# LVGL_Free_RTOS.net
KiCad netlist of a schematic drawn in EasyEDA Pro
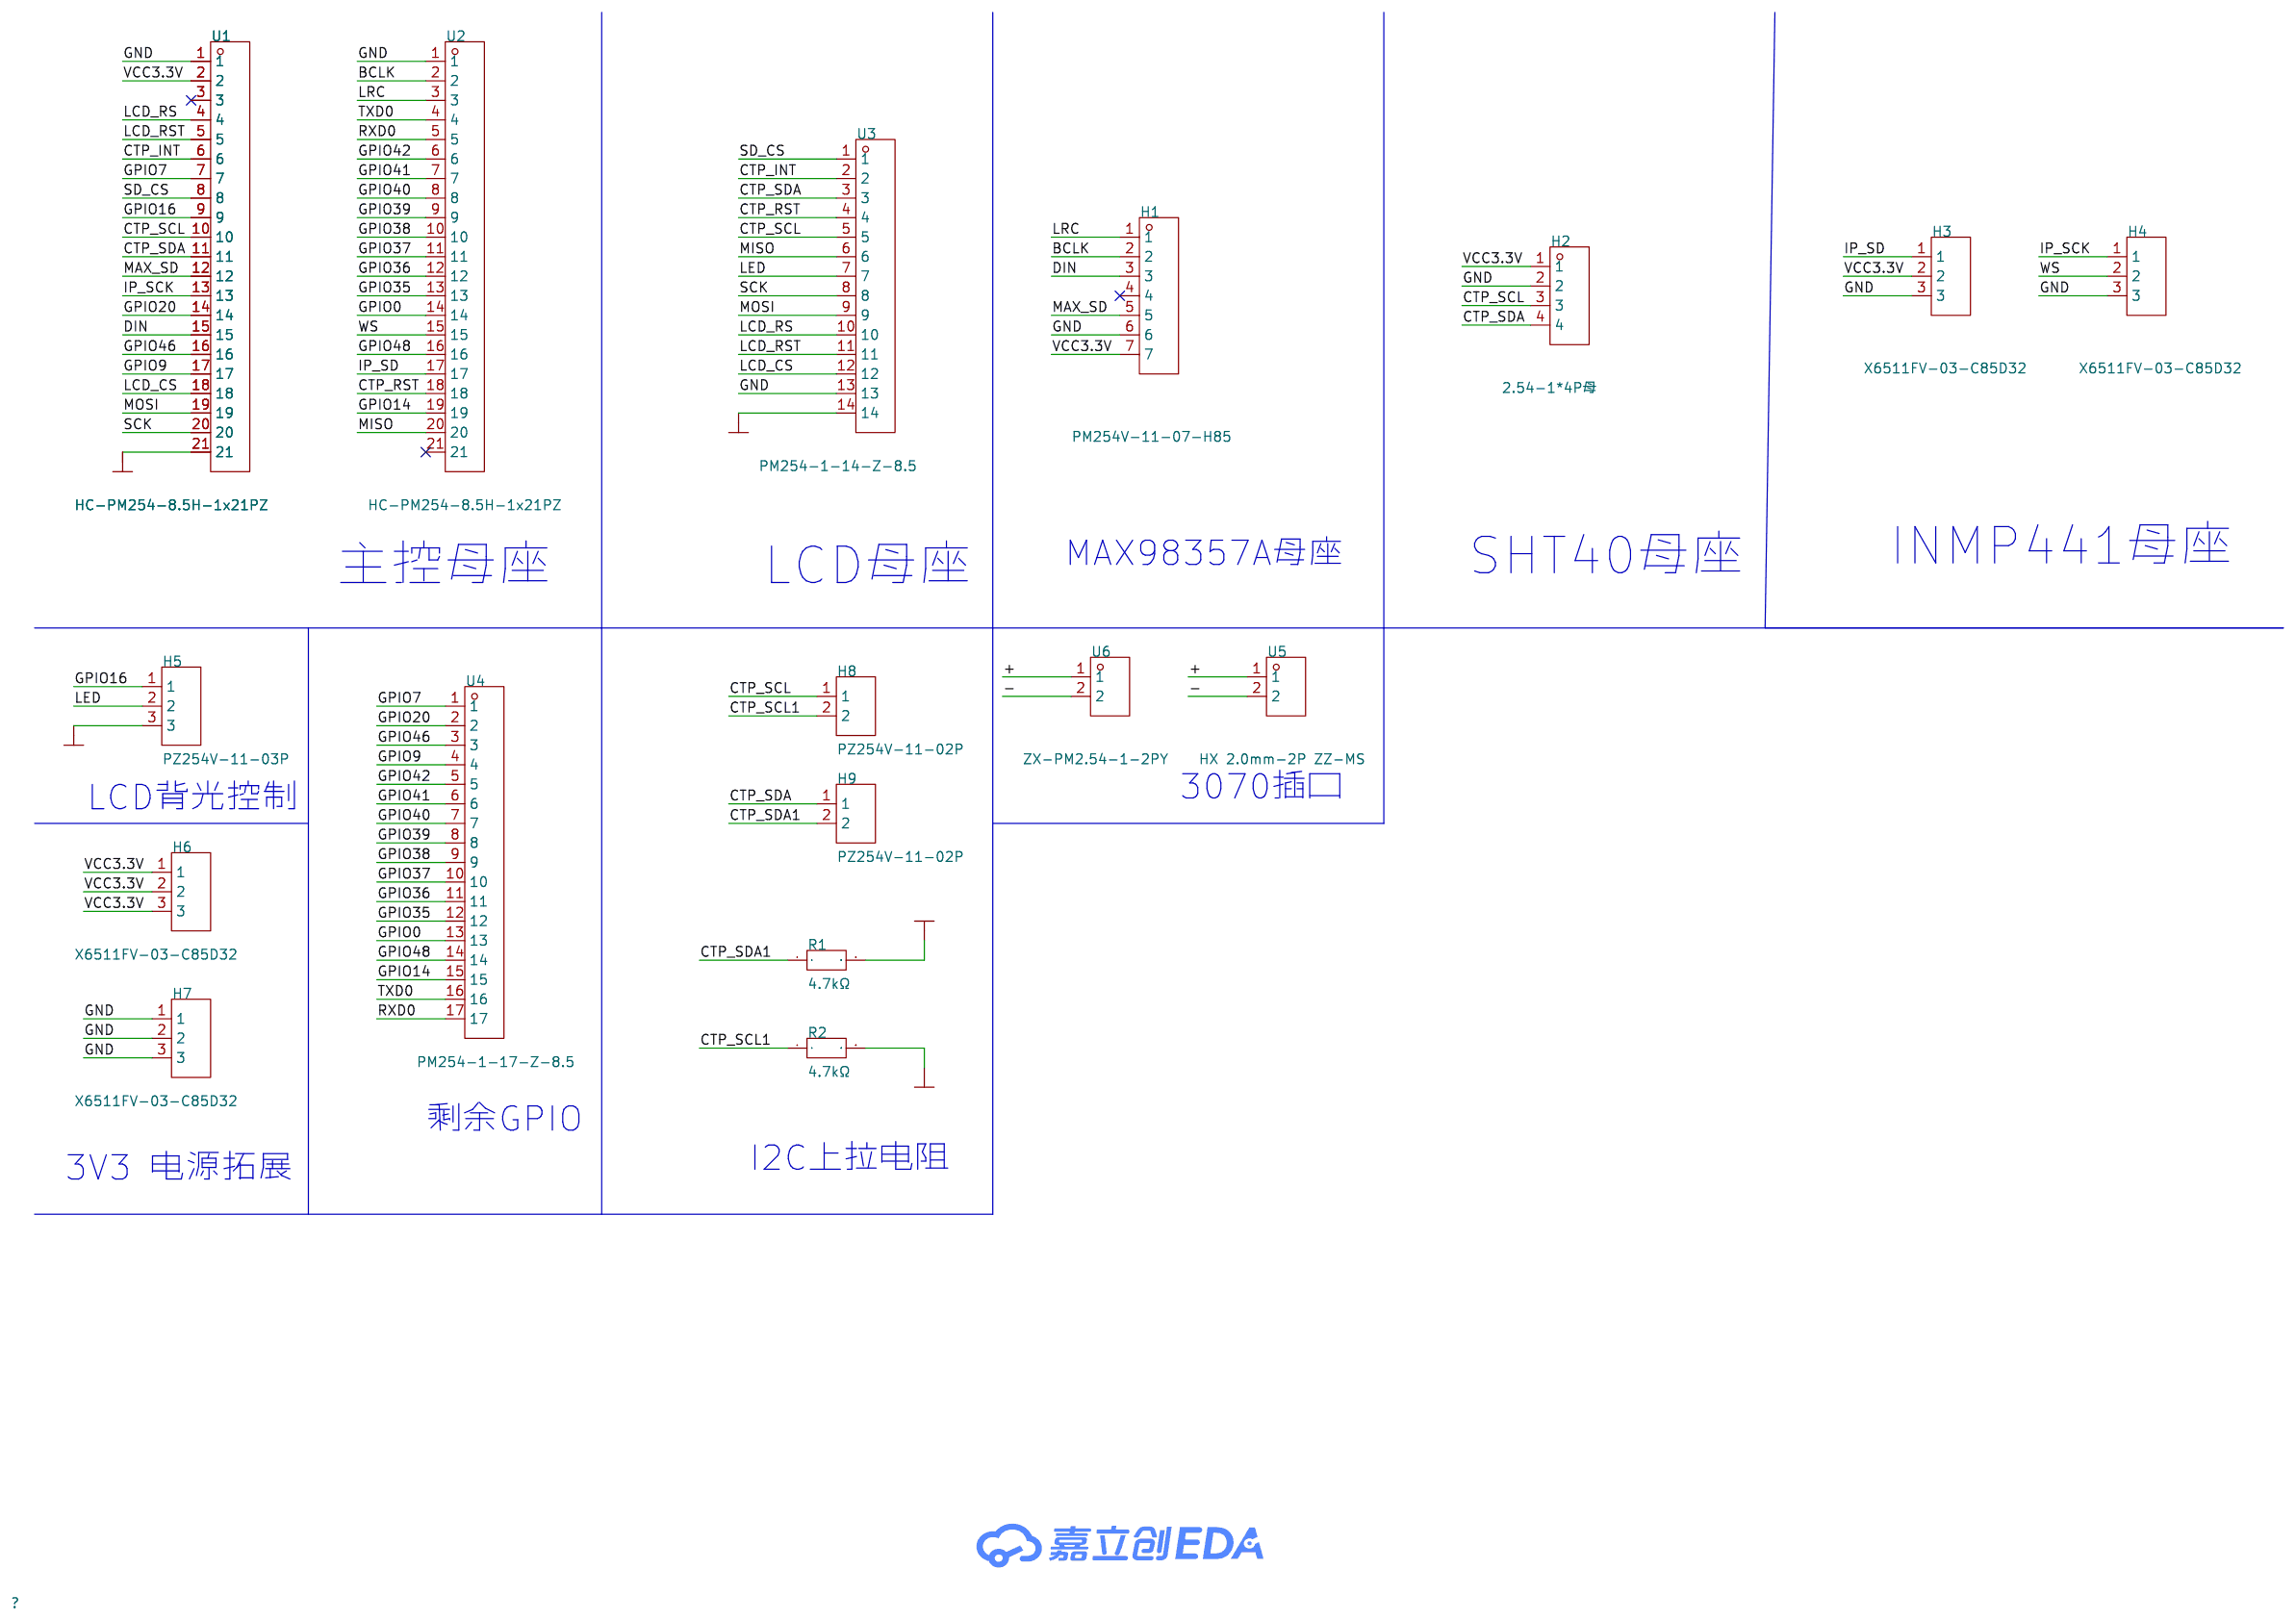
[diagram p0: schematic sheet]

(export (version "E")
  (design (tool "Eeschema 10.0.6"))
  (components
    (comp (ref "H1")
      (value "PM254V-11-07-H85")
      (footprint "easyedapro:HDR-TH_7P-P2.54-V-F")
      (fields (field (name "Manufacturer") "XFCN(兴飞)"))
      (libsource (lib "easyedapro") (part "PM254V-11-07-H85"))
    )
    (comp (ref "H2")
      (value "2.54-1*4P母")
      (footprint "easyedapro:HDR-TH_4P-P2.54-V-F")
      (fields (field (name "Manufacturer") "BOOMELE(博穆精密)"))
      (libsource (lib "easyedapro") (part "2.54-1*4P母"))
    )
    (comp (ref "H3")
      (value "X6511FV-03-C85D32")
      (footprint "easyedapro:HDR-TH_3P-P2.54-V-F")
      (fields (field (name "Manufacturer") "XKB Connection(中国星坤)"))
      (libsource (lib "easyedapro") (part "X6511FV-03-C85D32"))
    )
    (comp (ref "H4")
      (value "X6511FV-03-C85D32")
      (footprint "easyedapro:HDR-TH_3P-P2.54-V-F")
      (fields (field (name "Manufacturer") "XKB Connection(中国星坤)"))
      (libsource (lib "easyedapro") (part "X6511FV-03-C85D32"))
    )
    (comp (ref "H5")
      (value "PZ254V-11-03P")
      (footprint "easyedapro:HDR-TH_3P-P2.54-V-M")
      (fields (field (name "Manufacturer") "XFCN(兴飞)"))
      (libsource (lib "easyedapro") (part "PZ254V-11-03P_C2937625"))
    )
    (comp (ref "H6")
      (value "X6511FV-03-C85D32")
      (footprint "easyedapro:HDR-TH_3P-P2.54-V-F")
      (fields (field (name "Manufacturer") "XKB Connection(中国星坤)"))
      (libsource (lib "easyedapro") (part "X6511FV-03-C85D32"))
    )
    (comp (ref "H7")
      (value "X6511FV-03-C85D32")
      (footprint "easyedapro:HDR-TH_3P-P2.54-V-F")
      (fields (field (name "Manufacturer") "XKB Connection(中国星坤)"))
      (libsource (lib "easyedapro") (part "X6511FV-03-C85D32"))
    )
    (comp (ref "H8")
      (value "PZ254V-11-02P")
      (footprint "easyedapro:HDR-TH_2P-P2.54-V-M")
      (fields (field (name "Manufacturer") "XFCN(兴飞)"))
      (libsource (lib "easyedapro") (part "PZ254V-11-02P"))
    )
    (comp (ref "H9")
      (value "PZ254V-11-02P")
      (footprint "easyedapro:HDR-TH_2P-P2.54-V-M")
      (fields (field (name "Manufacturer") "XFCN(兴飞)"))
      (libsource (lib "easyedapro") (part "PZ254V-11-02P"))
    )
    (comp (ref "R1")
      (value "4.7kΩ")
      (footprint "easyedapro:R0603")
      (description "电阻类型:厚膜电阻;阻值:4.7kΩ;精度:±5%;功率:100mW;工作电压:75V;温度系数:±100ppm/°C;")
      (fields (field (name "Manufacturer Part") "RCA034K7JLF") (field (name "Manufacturer") "HKR(香港电阻)"))
      (libsource (lib "easyedapro") (part "RCA034K7JLF"))
    )
    (comp (ref "R2")
      (value "4.7kΩ")
      (footprint "easyedapro:R0603")
      (description "电阻类型:厚膜电阻;阻值:4.7kΩ;精度:±5%;功率:100mW;工作电压:75V;温度系数:±100ppm/°C;")
      (fields (field (name "Manufacturer Part") "RCA034K7JLF") (field (name "Manufacturer") "HKR(香港电阻)"))
      (libsource (lib "easyedapro") (part "RCA034K7JLF"))
    )
    (comp (ref "U1")
      (value "HC-PM254-8.5H-1x21PZ")
      (footprint "easyedapro:HDR-TH_21P-P2.54-V-F_1")
      (fields (field (name "Manufacturer") "HC(虹成电子)"))
      (libsource (lib "easyedapro") (part "HC-PM254-8.5H-1X21PZ"))
    )
    (comp (ref "U2")
      (value "HC-PM254-8.5H-1x21PZ")
      (footprint "easyedapro:HDR-TH_21P-P2.54-V-F_1")
      (fields (field (name "Manufacturer") "HC(虹成电子)"))
      (libsource (lib "easyedapro") (part "HC-PM254-8.5H-1X21PZ"))
    )
    (comp (ref "U3")
      (value "PM254-1-14-Z-8.5")
      (footprint "easyedapro:HDR-TH_14P-P2.54-V-F-1")
      (fields (field (name "Manufacturer") "HCTL(华灿天禄)"))
      (libsource (lib "easyedapro") (part "PM254-1-14-Z-8.5"))
    )
    (comp (ref "U4")
      (value "PM254-1-17-Z-8.5")
      (footprint "easyedapro:HDR-TH_17P-P2.54-V-F")
      (fields (field (name "Manufacturer") "HCTL(华灿天禄)"))
      (libsource (lib "easyedapro") (part "PM254-1-17-Z-8.5"))
    )
    (comp (ref "U5")
      (value "HX 2.0mm-2P ZZ-MS")
      (footprint "easyedapro:CONN-TH_2P-P2.00_HX-2.0MM-2P-ZZ")
      (fields (field (name "Manufacturer") "hanxia(韩下)"))
      (libsource (lib "easyedapro") (part "HX 2.0MM-2P ZZ-MS"))
    )
    (comp (ref "U6")
      (value "ZX-PM2.54-1-2PY")
      (footprint "easyedapro:HDR-TH_2P-P2.54-V-F")
      (fields (field (name "Manufacturer") "Megastar(兆星)"))
      (libsource (lib "easyedapro") (part "ZX-PM2.54-1-2PY"))
    )
  )
  (nets
    (net (code "1") (name "/+") (class "Default")
      (node (ref "U5") (pin "1") (pinfunction "1_1") (pintype "unspecified"))
      (node (ref "U6") (pin "1") (pinfunction "1_1") (pintype "unspecified"))
    )
    (net (code "2") (name "/-") (class "Default")
      (node (ref "U5") (pin "2") (pinfunction "2_2") (pintype "unspecified"))
      (node (ref "U6") (pin "2") (pinfunction "2_2") (pintype "unspecified"))
    )
    (net (code "3") (name "/BCLK") (class "Default")
      (node (ref "H1") (pin "2") (pinfunction "2_2") (pintype "unspecified"))
      (node (ref "U2") (pin "2") (pinfunction "2_2") (pintype "unspecified"))
    )
    (net (code "4") (name "/CTP_INT") (class "Default")
      (node (ref "U1") (pin "6") (pinfunction "6_6") (pintype "unspecified"))
      (node (ref "U3") (pin "2") (pinfunction "2_2") (pintype "unspecified"))
    )
    (net (code "5") (name "/CTP_RST") (class "Default")
      (node (ref "U2") (pin "18") (pinfunction "18_18") (pintype "unspecified"))
      (node (ref "U3") (pin "4") (pinfunction "4_4") (pintype "unspecified"))
    )
    (net (code "6") (name "/CTP_SCL") (class "Default")
      (node (ref "H2") (pin "3") (pinfunction "3_3") (pintype "unspecified"))
      (node (ref "H8") (pin "1") (pinfunction "1_1") (pintype "unspecified"))
      (node (ref "U1") (pin "10") (pinfunction "10_10") (pintype "unspecified"))
      (node (ref "U3") (pin "5") (pinfunction "5_5") (pintype "unspecified"))
    )
    (net (code "7") (name "/CTP_SCL1") (class "Default")
      (node (ref "H8") (pin "2") (pinfunction "2_2") (pintype "unspecified"))
      (node (ref "R2") (pin "1") (pinfunction "1_1") (pintype "unspecified"))
    )
    (net (code "8") (name "/CTP_SDA") (class "Default")
      (node (ref "H2") (pin "4") (pinfunction "4_4") (pintype "unspecified"))
      (node (ref "H9") (pin "1") (pinfunction "1_1") (pintype "unspecified"))
      (node (ref "U1") (pin "11") (pinfunction "11_11") (pintype "unspecified"))
      (node (ref "U3") (pin "3") (pinfunction "3_3") (pintype "unspecified"))
    )
    (net (code "9") (name "/CTP_SDA1") (class "Default")
      (node (ref "H9") (pin "2") (pinfunction "2_2") (pintype "unspecified"))
      (node (ref "R1") (pin "1") (pinfunction "1_1") (pintype "unspecified"))
    )
    (net (code "10") (name "/DIN") (class "Default")
      (node (ref "H1") (pin "3") (pinfunction "3_3") (pintype "unspecified"))
      (node (ref "U1") (pin "15") (pinfunction "15_15") (pintype "unspecified"))
    )
    (net (code "11") (name "/GND") (class "Default")
      (node (ref "H1") (pin "6") (pinfunction "6_6") (pintype "unspecified"))
      (node (ref "H2") (pin "2") (pinfunction "2_2") (pintype "unspecified"))
      (node (ref "H3") (pin "3") (pinfunction "3_3") (pintype "unspecified"))
      (node (ref "H4") (pin "3") (pinfunction "3_3") (pintype "unspecified"))
      (node (ref "H7") (pin "1") (pinfunction "1_1") (pintype "unspecified"))
      (node (ref "H7") (pin "2") (pinfunction "2_2") (pintype "unspecified"))
      (node (ref "H7") (pin "3") (pinfunction "3_3") (pintype "unspecified"))
      (node (ref "U1") (pin "1") (pinfunction "1_1") (pintype "unspecified"))
      (node (ref "U2") (pin "1") (pinfunction "1_1") (pintype "unspecified"))
      (node (ref "U3") (pin "13") (pinfunction "13_13") (pintype "unspecified"))
    )
    (net (code "12") (name "/GPIO0") (class "Default")
      (node (ref "U2") (pin "14") (pinfunction "14_14") (pintype "unspecified"))
      (node (ref "U4") (pin "13") (pinfunction "13_13") (pintype "unspecified"))
    )
    (net (code "13") (name "/GPIO7") (class "Default")
      (node (ref "U1") (pin "7") (pinfunction "7_7") (pintype "unspecified"))
      (node (ref "U4") (pin "1") (pinfunction "1_1") (pintype "unspecified"))
    )
    (net (code "14") (name "/GPIO9") (class "Default")
      (node (ref "U1") (pin "17") (pinfunction "17_17") (pintype "unspecified"))
      (node (ref "U4") (pin "4") (pinfunction "4_4") (pintype "unspecified"))
    )
    (net (code "15") (name "/GPIO14") (class "Default")
      (node (ref "U2") (pin "19") (pinfunction "19_19") (pintype "unspecified"))
      (node (ref "U4") (pin "15") (pinfunction "15_15") (pintype "unspecified"))
    )
    (net (code "16") (name "/GPIO16") (class "Default")
      (node (ref "H5") (pin "1") (pinfunction "1_1") (pintype "unspecified"))
      (node (ref "U1") (pin "9") (pinfunction "9_9") (pintype "unspecified"))
    )
    (net (code "17") (name "/GPIO20") (class "Default")
      (node (ref "U1") (pin "14") (pinfunction "14_14") (pintype "unspecified"))
      (node (ref "U4") (pin "2") (pinfunction "2_2") (pintype "unspecified"))
    )
    (net (code "18") (name "/GPIO35") (class "Default")
      (node (ref "U2") (pin "13") (pinfunction "13_13") (pintype "unspecified"))
      (node (ref "U4") (pin "12") (pinfunction "12_12") (pintype "unspecified"))
    )
    (net (code "19") (name "/GPIO36") (class "Default")
      (node (ref "U2") (pin "12") (pinfunction "12_12") (pintype "unspecified"))
      (node (ref "U4") (pin "11") (pinfunction "11_11") (pintype "unspecified"))
    )
    (net (code "20") (name "/GPIO37") (class "Default")
      (node (ref "U2") (pin "11") (pinfunction "11_11") (pintype "unspecified"))
      (node (ref "U4") (pin "10") (pinfunction "10_10") (pintype "unspecified"))
    )
    (net (code "21") (name "/GPIO38") (class "Default")
      (node (ref "U2") (pin "10") (pinfunction "10_10") (pintype "unspecified"))
      (node (ref "U4") (pin "9") (pinfunction "9_9") (pintype "unspecified"))
    )
    (net (code "22") (name "/GPIO39") (class "Default")
      (node (ref "U2") (pin "9") (pinfunction "9_9") (pintype "unspecified"))
      (node (ref "U4") (pin "8") (pinfunction "8_8") (pintype "unspecified"))
    )
    (net (code "23") (name "/GPIO40") (class "Default")
      (node (ref "U2") (pin "8") (pinfunction "8_8") (pintype "unspecified"))
      (node (ref "U4") (pin "7") (pinfunction "7_7") (pintype "unspecified"))
    )
    (net (code "24") (name "/GPIO41") (class "Default")
      (node (ref "U2") (pin "7") (pinfunction "7_7") (pintype "unspecified"))
      (node (ref "U4") (pin "6") (pinfunction "6_6") (pintype "unspecified"))
    )
    (net (code "25") (name "/GPIO42") (class "Default")
      (node (ref "U2") (pin "6") (pinfunction "6_6") (pintype "unspecified"))
      (node (ref "U4") (pin "5") (pinfunction "5_5") (pintype "unspecified"))
    )
    (net (code "26") (name "/GPIO46") (class "Default")
      (node (ref "U1") (pin "16") (pinfunction "16_16") (pintype "unspecified"))
      (node (ref "U4") (pin "3") (pinfunction "3_3") (pintype "unspecified"))
    )
    (net (code "27") (name "/GPIO48") (class "Default")
      (node (ref "U2") (pin "16") (pinfunction "16_16") (pintype "unspecified"))
      (node (ref "U4") (pin "14") (pinfunction "14_14") (pintype "unspecified"))
    )
    (net (code "28") (name "/IP_SCK") (class "Default")
      (node (ref "H4") (pin "1") (pinfunction "1_1") (pintype "unspecified"))
      (node (ref "U1") (pin "13") (pinfunction "13_13") (pintype "unspecified"))
    )
    (net (code "29") (name "/IP_SD") (class "Default")
      (node (ref "H3") (pin "1") (pinfunction "1_1") (pintype "unspecified"))
      (node (ref "U2") (pin "17") (pinfunction "17_17") (pintype "unspecified"))
    )
    (net (code "30") (name "/LCD_CS") (class "Default")
      (node (ref "U1") (pin "18") (pinfunction "18_18") (pintype "unspecified"))
      (node (ref "U3") (pin "12") (pinfunction "12_12") (pintype "unspecified"))
    )
    (net (code "31") (name "/LCD_RS") (class "Default")
      (node (ref "U1") (pin "4") (pinfunction "4_4") (pintype "unspecified"))
      (node (ref "U3") (pin "10") (pinfunction "10_10") (pintype "unspecified"))
    )
    (net (code "32") (name "/LCD_RST") (class "Default")
      (node (ref "U1") (pin "5") (pinfunction "5_5") (pintype "unspecified"))
      (node (ref "U3") (pin "11") (pinfunction "11_11") (pintype "unspecified"))
    )
    (net (code "33") (name "/LED") (class "Default")
      (node (ref "H5") (pin "2") (pinfunction "2_2") (pintype "unspecified"))
      (node (ref "U3") (pin "7") (pinfunction "7_7") (pintype "unspecified"))
    )
    (net (code "34") (name "/LRC") (class "Default")
      (node (ref "H1") (pin "1") (pinfunction "1_1") (pintype "unspecified"))
      (node (ref "U2") (pin "3") (pinfunction "3_3") (pintype "unspecified"))
    )
    (net (code "35") (name "/MAX_SD") (class "Default")
      (node (ref "H1") (pin "5") (pinfunction "5_5") (pintype "unspecified"))
      (node (ref "U1") (pin "12") (pinfunction "12_12") (pintype "unspecified"))
    )
    (net (code "36") (name "/MISO") (class "Default")
      (node (ref "U2") (pin "20") (pinfunction "20_20") (pintype "unspecified"))
      (node (ref "U3") (pin "6") (pinfunction "6_6") (pintype "unspecified"))
    )
    (net (code "37") (name "/MOSI") (class "Default")
      (node (ref "U1") (pin "19") (pinfunction "19_19") (pintype "unspecified"))
      (node (ref "U3") (pin "9") (pinfunction "9_9") (pintype "unspecified"))
    )
    (net (code "38") (name "/RXD0") (class "Default")
      (node (ref "U2") (pin "5") (pinfunction "5_5") (pintype "unspecified"))
      (node (ref "U4") (pin "17") (pinfunction "17_17") (pintype "unspecified"))
    )
    (net (code "39") (name "/SCK") (class "Default")
      (node (ref "U1") (pin "20") (pinfunction "20_20") (pintype "unspecified"))
      (node (ref "U3") (pin "8") (pinfunction "8_8") (pintype "unspecified"))
    )
    (net (code "40") (name "/SD_CS") (class "Default")
      (node (ref "U1") (pin "8") (pinfunction "8_8") (pintype "unspecified"))
      (node (ref "U3") (pin "1") (pinfunction "1_1") (pintype "unspecified"))
    )
    (net (code "41") (name "/TXD0") (class "Default")
      (node (ref "U2") (pin "4") (pinfunction "4_4") (pintype "unspecified"))
      (node (ref "U4") (pin "16") (pinfunction "16_16") (pintype "unspecified"))
    )
    (net (code "42") (name "/VCC3.3V") (class "Default")
      (node (ref "H1") (pin "7") (pinfunction "7_7") (pintype "unspecified"))
      (node (ref "H2") (pin "1") (pinfunction "1_1") (pintype "unspecified"))
      (node (ref "H3") (pin "2") (pinfunction "2_2") (pintype "unspecified"))
      (node (ref "H6") (pin "1") (pinfunction "1_1") (pintype "unspecified"))
      (node (ref "H6") (pin "2") (pinfunction "2_2") (pintype "unspecified"))
      (node (ref "H6") (pin "3") (pinfunction "3_3") (pintype "unspecified"))
      (node (ref "U1") (pin "2") (pinfunction "2_2") (pintype "unspecified"))
    )
    (net (code "43") (name "/WS") (class "Default")
      (node (ref "H4") (pin "2") (pinfunction "2_2") (pintype "unspecified"))
      (node (ref "U2") (pin "15") (pinfunction "15_15") (pintype "unspecified"))
    )
    (net (code "44") (name "3V3") (class "Default")
      (node (ref "H5") (pin "3") (pinfunction "3_3") (pintype "unspecified"))
      (node (ref "R1") (pin "2") (pinfunction "2_2") (pintype "unspecified"))
      (node (ref "R2") (pin "2") (pinfunction "2_2") (pintype "unspecified"))
      (node (ref "U1") (pin "21") (pinfunction "21_21") (pintype "unspecified"))
      (node (ref "U3") (pin "14") (pinfunction "14_14") (pintype "unspecified"))
    )
    (net (code "45") (name "unconnected-(H1-Pad4)") (class "Default")
      (node (ref "H1") (pin "4") (pinfunction "4_4") (pintype "unspecified+no_connect"))
    )
    (net (code "46") (name "unconnected-(U1-Pad3)") (class "Default")
      (node (ref "U1") (pin "3") (pinfunction "3_3") (pintype "unspecified+no_connect"))
    )
    (net (code "47") (name "unconnected-(U2-Pad21)") (class "Default")
      (node (ref "U2") (pin "21") (pinfunction "21_21") (pintype "unspecified+no_connect"))
    )
  )
)
